# attiny1l_alt.net
KiCad netlist of a schematic drawn in EAGLE
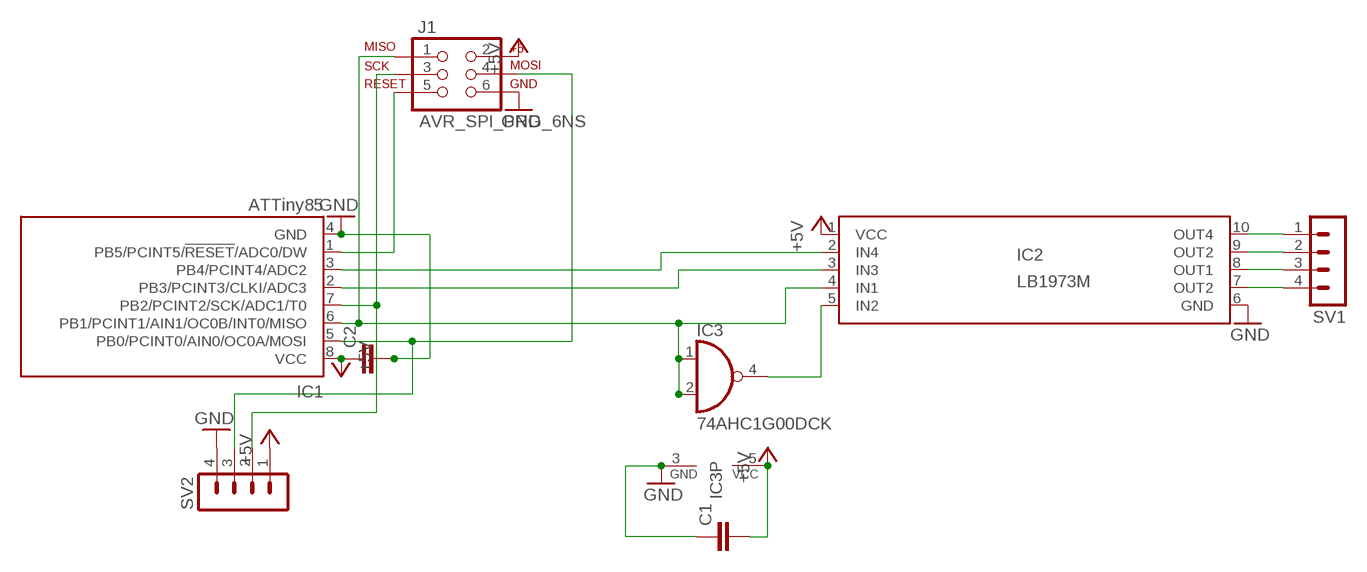
[diagram p0: schematic, sheet 1]

(export (version "E")
  (design (tool "Eeschema 10.0.6"))
  (components
    (comp (ref "C1")
      (value "C-EUC0805")
      (footprint "eagle-import:C0805")
      (libsource (lib "eagle-import") (part "C-EUC0805"))
    )
    (comp (ref "C2")
      (value "C-EUC0805")
      (footprint "eagle-import:C0805")
      (libsource (lib "eagle-import") (part "C-EUC0805"))
    )
    (comp (ref "IC1")
      (value "ATTiny85")
      (footprint "eagle-import:8S2")
      (fields (field (name "MPN") "ATTINY13-20SU"))
      (libsource (lib "eagle-import") (part "TINY13SU-20"))
    )
    (comp (ref "IC2")
      (value "LB1973M")
      (footprint "eagle-import:SSOP10")
      (libsource (lib "eagle-import") (part "LB1973M"))
    )
    (comp (ref "IC3")
      (value "74AHC1G00DCK")
      (footprint "eagle-import:SC70-5")
      (libsource (lib "eagle-import") (part "741G00DCKAHC"))
    )
    (comp (ref "J1")
      (value "AVR_SPI_PRG_6NS")
      (footprint "eagle-import:2X3-NS")
      (libsource (lib "eagle-import") (part "AVR_SPI_PRG_6NS"))
    )
    (comp (ref "SV1")
      (value "MA04-1")
      (footprint "eagle-import:MA04-1")
      (libsource (lib "eagle-import") (part "MA04-1"))
    )
    (comp (ref "SV2")
      (value "MA04-1")
      (footprint "eagle-import:MA04-1")
      (libsource (lib "eagle-import") (part "MA04-1"))
    )
  )
  (nets
    (net (code "1") (name "+5V") (class "Default")
      (node (ref "C1") (pin "2") (pinfunction "2_2") (pintype "passive"))
      (node (ref "C2") (pin "1") (pinfunction "1_1") (pintype "passive"))
      (node (ref "IC1") (pin "8") (pinfunction "VCC_8") (pintype "power_in"))
      (node (ref "IC2") (pin "1") (pinfunction "VCC_1") (pintype "power_in"))
      (node (ref "IC3") (pin "5") (pinfunction "VCC_5") (pintype "power_in"))
      (node (ref "J1") (pin "2") (pinfunction "2_2") (pintype "passive"))
      (node (ref "SV2") (pin "1") (pinfunction "1_1") (pintype "passive"))
    )
    (net (code "2") (name "GND") (class "Default")
      (node (ref "C1") (pin "1") (pinfunction "1_1") (pintype "passive"))
      (node (ref "C2") (pin "2") (pinfunction "2_2") (pintype "passive"))
      (node (ref "IC1") (pin "4") (pinfunction "GND_4") (pintype "power_in"))
      (node (ref "IC2") (pin "6") (pinfunction "GND_6") (pintype "power_in"))
      (node (ref "IC3") (pin "3") (pinfunction "GND_3") (pintype "power_in"))
      (node (ref "J1") (pin "6") (pinfunction "6_6") (pintype "passive"))
      (node (ref "SV2") (pin "4") (pinfunction "4_4") (pintype "passive"))
    )
    (net (code "3") (name "Net-(IC1-PB0{slash}PCINT0{slash}AIN0{slash}OC0A{slash}MOSI)") (class "Default")
      (node (ref "IC1") (pin "5") (pinfunction "PB0/PCINT0/AIN0/OC0A/MOSI_5") (pintype "bidirectional"))
      (node (ref "J1") (pin "4") (pinfunction "4_4") (pintype "passive"))
      (node (ref "SV2") (pin "3") (pinfunction "3_3") (pintype "passive"))
    )
    (net (code "4") (name "Net-(IC1-PB1{slash}PCINT1{slash}AIN1{slash}OC0B{slash}INT0{slash}MISO)") (class "Default")
      (node (ref "IC1") (pin "6") (pinfunction "PB1/PCINT1/AIN1/OC0B/INT0/MISO_6") (pintype "bidirectional"))
      (node (ref "IC2") (pin "4") (pinfunction "IN1_4") (pintype "input"))
      (node (ref "IC3") (pin "1") (pinfunction "I0_1") (pintype "input"))
      (node (ref "IC3") (pin "2") (pinfunction "I1_2") (pintype "input"))
      (node (ref "J1") (pin "1") (pinfunction "1_1") (pintype "passive"))
    )
    (net (code "5") (name "Net-(IC1-PB2{slash}PCINT2{slash}SCK{slash}ADC1{slash}T0)") (class "Default")
      (node (ref "IC1") (pin "7") (pinfunction "PB2/PCINT2/SCK/ADC1/T0_7") (pintype "bidirectional"))
      (node (ref "J1") (pin "3") (pinfunction "3_3") (pintype "passive"))
      (node (ref "SV2") (pin "2") (pinfunction "2_2") (pintype "passive"))
    )
    (net (code "6") (name "Net-(IC1-PB3{slash}PCINT3{slash}CLKI{slash}ADC3)") (class "Default")
      (node (ref "IC1") (pin "2") (pinfunction "PB3/PCINT3/CLKI/ADC3_2") (pintype "bidirectional"))
      (node (ref "IC2") (pin "3") (pinfunction "IN3_3") (pintype "input"))
    )
    (net (code "7") (name "Net-(IC1-PB4{slash}PCINT4{slash}ADC2)") (class "Default")
      (node (ref "IC1") (pin "3") (pinfunction "PB4/PCINT4/ADC2_3") (pintype "bidirectional"))
      (node (ref "IC2") (pin "2") (pinfunction "IN4_2") (pintype "input"))
    )
    (net (code "8") (name "Net-(IC1-PB5{slash}PCINT5{slash}~{RESET}{slash}ADC0{slash}DW)") (class "Default")
      (node (ref "IC1") (pin "1") (pinfunction "PB5/PCINT5/~{RESET}/ADC0/DW_1") (pintype "bidirectional"))
      (node (ref "J1") (pin "5") (pinfunction "5_5") (pintype "passive"))
    )
    (net (code "9") (name "Net-(IC2-IN2)") (class "Default")
      (node (ref "IC2") (pin "5") (pinfunction "IN2_5") (pintype "input"))
      (node (ref "IC3") (pin "4") (pinfunction "O_4") (pintype "output"))
    )
    (net (code "10") (name "Net-(IC2-OUT1)") (class "Default")
      (node (ref "IC2") (pin "8") (pinfunction "OUT1_8") (pintype "output"))
      (node (ref "SV1") (pin "3") (pinfunction "3_3") (pintype "passive"))
    )
    (net (code "11") (name "Net-(IC2-OUT2-Pad7)") (class "Default")
      (node (ref "IC2") (pin "7") (pinfunction "OUT2_7") (pintype "output"))
      (node (ref "SV1") (pin "4") (pinfunction "4_4") (pintype "passive"))
    )
    (net (code "12") (name "Net-(IC2-OUT2-Pad9)") (class "Default")
      (node (ref "IC2") (pin "9") (pinfunction "OUT2_9") (pintype "output"))
      (node (ref "SV1") (pin "2") (pinfunction "2_2") (pintype "passive"))
    )
    (net (code "13") (name "Net-(IC2-OUT4)") (class "Default")
      (node (ref "IC2") (pin "10") (pinfunction "OUT4_10") (pintype "output"))
      (node (ref "SV1") (pin "1") (pinfunction "1_1") (pintype "passive"))
    )
  )
)
